# Top_Level.net
KiCad netlist of a schematic drawn in Altium Designer
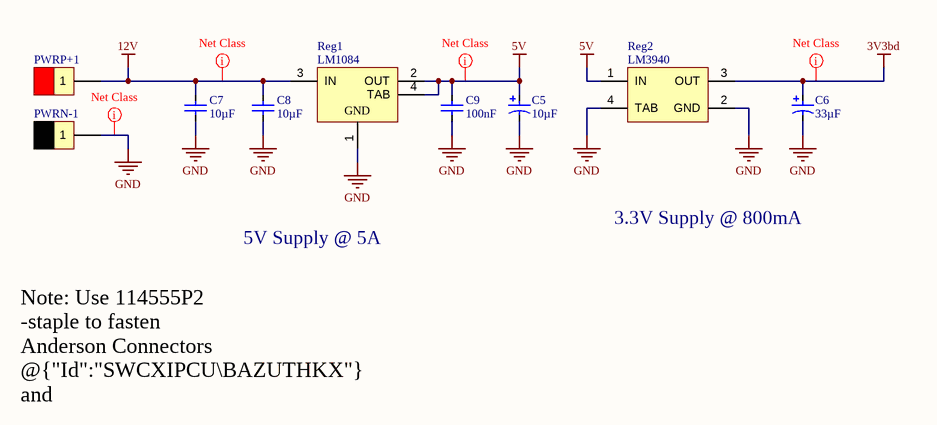
[diagram p0: Top_Level.SchDoc]

(export (version "E")
  (design (tool "Eeschema 10.0.6"))
  (components
    (comp (ref "C5")
      (value "10µF")
      (footprint "AVX-TPSB106K020R1000_L")
      (fields
        (field (name "MANUFACTURER") "Kyocera AVX")
        (field (name "MANUFACTURER PART NUMBER") "TPSB106K020R1000")
        (field (name "Comment") "CAP Polar 10uF")
      )
      (libsource (lib "MHH -  Altium Advanced Course A365 01") (part "CMP-00072-1"))
    )
    (comp (ref "C6")
      (value "33µF")
      (footprint "FP-TAJY-MFG")
      (fields
        (field (name "MANUFACTURER") "Kyocera AVX")
        (field (name "MANUFACTURER PART NUMBER") "TAJY336K020RNJ")
        (field (name "Comment") "CAP Polar 33uF")
      )
      (libsource (lib "MHH -  Altium Advanced Course A365 01") (part "CMP-00072-1"))
    )
    (comp (ref "C7")
      (value "10µF")
      (footprint "CAPC2013X135X45ML10T25")
      (fields
        (field (name "TOLERANCE") "10%")
        (field (name "MANUFACTURER") "Murata")
        (field (name "MANUFACTURER PART NUMBER") "GRM21BR61E106KA73L")
      )
      (libsource (lib "MHH -  Altium Advanced Course A365 01") (part "CMP-00043-1"))
    )
    (comp (ref "C8")
      (value "10µF")
      (footprint "CAPC2013X135X45ML10T25")
      (fields
        (field (name "TOLERANCE") "10%")
        (field (name "MANUFACTURER") "Murata")
        (field (name "MANUFACTURER PART NUMBER") "GRM21BR61E106KA73L")
      )
      (libsource (lib "MHH -  Altium Advanced Course A365 01") (part "CMP-00043-1"))
    )
    (comp (ref "C9")
      (value "100nF")
      (footprint "0603C_L")
      (fields
        (field (name "MANUFACTURER") "Yageo")
        (field (name "MANUFACTURER PART NUMBER") "CC0603ZRY5V9BB104")
        (field (name "Comment") "CAP 100nF")
      )
      (libsource (lib "MHH -  Altium Advanced Course A365 01") (part "CMP-00119-2"))
    )
    (comp (ref "PWRN-1")
      (value "Anderson Black 1Pin")
      (footprint "Anderson_BLK_RHT_BOT")
      (description "Anderson-1Pin BLK_PCB_RHT")
      (fields
        (field (name "MANUFACTURER") "Anderson Power")
        (field (name "MANUFACTURER PART NUMBER") "1327G6")
      )
      (libsource (lib "MHH -  Altium Advanced Course A365 01") (part "Anderson Black 1Pin"))
    )
    (comp (ref "PWRP+1")
      (value "Anderson RED 1Pin")
      (footprint "Anderson_RED_RHT_BOT")
      (description "Anderson-1Pin RED_PCB_RHT")
      (fields
        (field (name "MANUFACTURER") "Anderson Power")
        (field (name "MANUFACTURER PART NUMBER") "1377G2")
      )
      (libsource (lib "MHH -  Altium Advanced Course A365 01") (part "Anderson RED 1Pin"))
    )
    (comp (ref "Reg1")
      (value "LM1084")
      (footprint "KTT0003B_L")
      (description "5A Low Dropout Positive Regulators, 3-pin TO-263, Pb-Free")
      (fields
        (field (name "MANUFACTURER") "TI National Semiconductor")
        (field (name "PARTNUMBER") "LM1084IS-5.0/NOPB")
        (field (name "SOURCE") "WCT.SchLib")
        (field (name "AVAILABLE PREVIEW IMAGES") "2D")
      )
      (libsource (lib "MHH -  Altium Advanced Course A365 01") (part "LM1084"))
    )
    (comp (ref "Reg2")
      (value "LM3940")
      (footprint "SOT223")
      (description "1A Low Dropout Regulator for 5V to 3.3V Conversion, 4-pin SOT-223, Pb-Free")
      (fields
        (field (name "MANUFACTURER") "Texas Instruments")
        (field (name "MANUFACTURER PART NUMBER") "LM3940IMP-3.3/NOPB")
        (field (name "SOURCE") "WCT.SchLib")
      )
      (libsource (lib "MHH -  Altium Advanced Course A365 01") (part "LM3940"))
    )
  )
  (nets
    (net (code "1") (name "3V3bd") (class "Default")
      (node (ref "C6") (pin "2") (pinfunction "2_2") (pintype "passive"))
      (node (ref "Reg2") (pin "3") (pinfunction "OUT_3") (pintype "power_in"))
    )
    (net (code "2") (name "5V") (class "Default")
      (node (ref "C5") (pin "2") (pinfunction "2_2") (pintype "passive"))
      (node (ref "C9") (pin "2") (pinfunction "2_2") (pintype "passive"))
      (node (ref "Reg1") (pin "2") (pinfunction "OUT_2") (pintype "power_in"))
      (node (ref "Reg1") (pin "4") (pinfunction "TAB_4") (pintype "power_in"))
      (node (ref "Reg2") (pin "1") (pinfunction "IN_1") (pintype "power_in"))
    )
    (net (code "3") (name "12V") (class "Default")
      (node (ref "C7") (pin "2") (pinfunction "2_2") (pintype "passive"))
      (node (ref "C8") (pin "2") (pinfunction "2_2") (pintype "passive"))
      (node (ref "PWRP+1") (pin "1") (pinfunction "1_1") (pintype "passive"))
      (node (ref "Reg1") (pin "3") (pinfunction "IN_3") (pintype "power_in"))
    )
    (net (code "4") (name "GND") (class "Default")
      (node (ref "C5") (pin "1") (pinfunction "1_1") (pintype "passive"))
      (node (ref "C6") (pin "1") (pinfunction "1_1") (pintype "passive"))
      (node (ref "C7") (pin "1") (pinfunction "1_1") (pintype "passive"))
      (node (ref "C8") (pin "1") (pinfunction "1_1") (pintype "passive"))
      (node (ref "C9") (pin "1") (pinfunction "1_1") (pintype "passive"))
      (node (ref "PWRN-1") (pin "1") (pinfunction "1_1") (pintype "passive"))
      (node (ref "Reg1") (pin "1") (pinfunction "GND_1") (pintype "power_in"))
      (node (ref "Reg2") (pin "2") (pinfunction "GND_2") (pintype "power_in"))
      (node (ref "Reg2") (pin "4") (pinfunction "TAB_4") (pintype "power_in"))
    )
  )
)
